# BatmanDetector.net
KiCad netlist of a schematic drawn in EAGLE
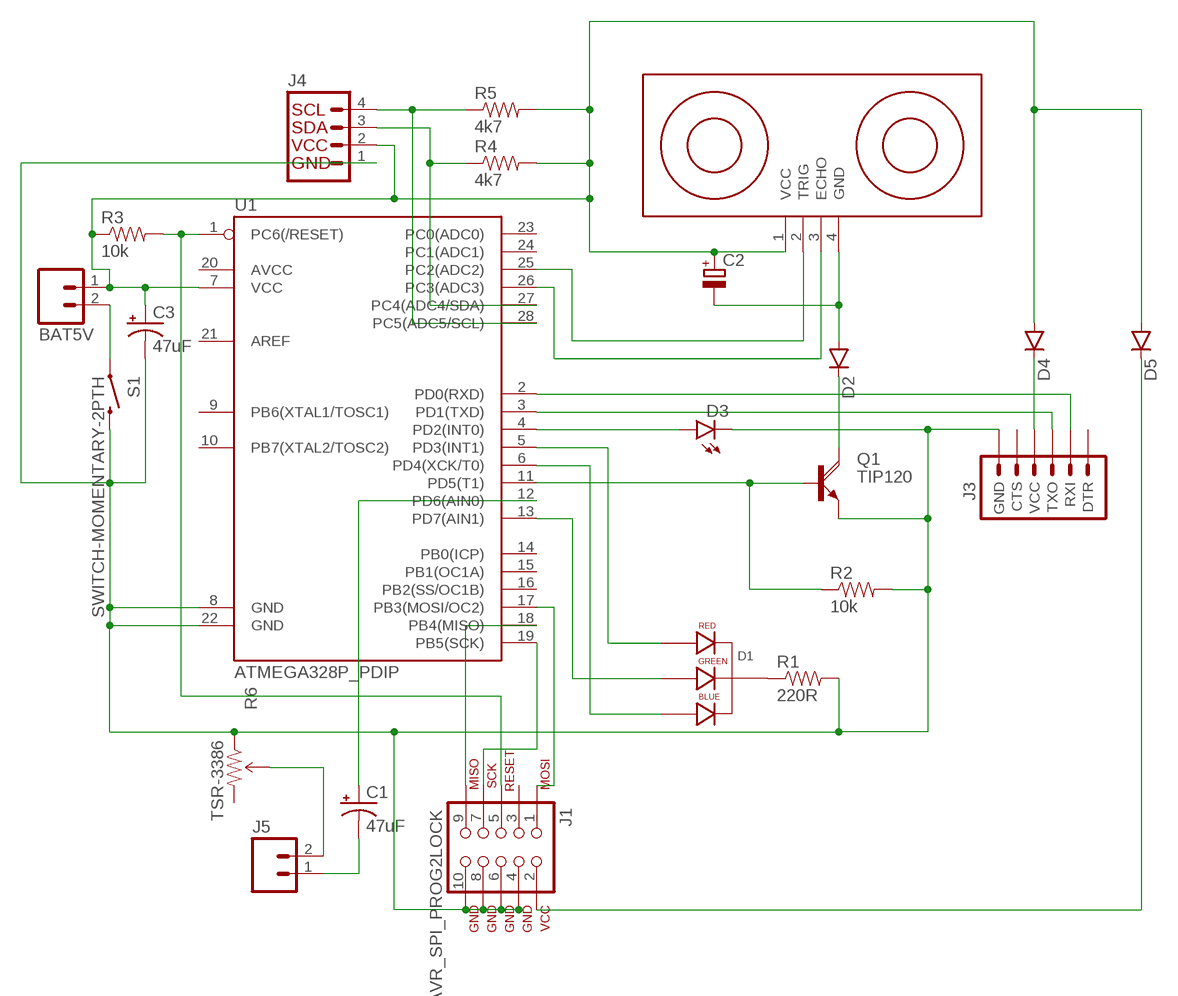
[diagram p0: schematic, sheet 1]

(export (version "E")
  (design (tool "Eeschema 10.0.6"))
  (components
    (comp (ref "BAT5V")
      (value "M02JST-PTH-VERT")
      (footprint "eagle-import:JST-2-PTH-VERT")
      (libsource (lib "eagle-import") (part "M02JST-PTH-VERT"))
    )
    (comp (ref "C1")
      (value "47uF")
      (footprint "eagle-import:CPOL-RADIAL-10UF-25V")
      (libsource (lib "eagle-import") (part "CAP_POLPTH2"))
    )
    (comp (ref "C2")
      (value "CPOL-EUE15-5AXIAL")
      (footprint "eagle-import:E15-5")
      (libsource (lib "eagle-import") (part "CPOL-EUE15-5AXIAL"))
    )
    (comp (ref "C3")
      (value "47uF")
      (footprint "eagle-import:CPOL-RADIAL-10UF-25V")
      (libsource (lib "eagle-import") (part "CAP_POLPTH2"))
    )
    (comp (ref "D1")
      (value "LED-RGB-CC-THRUDIFFUSE")
      (footprint "eagle-import:LED-RGB-THRU")
      (libsource (lib "eagle-import") (part "LED-RGB-CC-THRUDIFFUSE"))
    )
    (comp (ref "D2")
      (value "DIODE1N4148")
      (footprint "eagle-import:DIODE-1N4148")
      (libsource (lib "eagle-import") (part "DIODE1N4148"))
    )
    (comp (ref "D3")
      (value "LED-3MM-NO_SILK")
      (footprint "eagle-import:LED3MM-NS")
      (libsource (lib "eagle-import") (part "LED-3MM-NO_SILK"))
    )
    (comp (ref "D4")
      (value "DIODE1N4148")
      (footprint "eagle-import:DIODE-1N4148")
      (libsource (lib "eagle-import") (part "DIODE1N4148"))
    )
    (comp (ref "D5")
      (value "DIODE1N4148")
      (footprint "eagle-import:DIODE-1N4148")
      (libsource (lib "eagle-import") (part "DIODE1N4148"))
    )
    (comp (ref "J1")
      (value "AVR_SPI_PROG2LOCK")
      (footprint "eagle-import:2X5-SHROUDED_LOCK")
      (libsource (lib "eagle-import") (part "AVR_SPI_PROG2LOCK"))
    )
    (comp (ref "J3")
      (value "ARDUINO_SERIAL_PROGRAMLONGPADS")
      (footprint "eagle-import:1X06_LONGPADS")
      (libsource (lib "eagle-import") (part "ARDUINO_SERIAL_PROGRAMLONGPADS"))
    )
    (comp (ref "J4")
      (value "I2C_STANDARD_NO_SILK")
      (footprint "eagle-import:1X04_NO_SILK")
      (libsource (lib "eagle-import") (part "I2C_STANDARD_NO_SILK"))
    )
    (comp (ref "J5")
      (value "M02PTH3")
      (footprint "eagle-import:1X02_LONGPADS")
      (libsource (lib "eagle-import") (part "M02PTH3"))
    )
    (comp (ref "Q1")
      (value "TIP120")
      (footprint "eagle-import:TO220AH")
      (libsource (lib "eagle-import") (part "TIP120"))
    )
    (comp (ref "R1")
      (value "220R")
      (footprint "eagle-import:AXIAL-0.3")
      (libsource (lib "eagle-import") (part "RESISTORAXIAL-0.3"))
    )
    (comp (ref "R2")
      (value "10k")
      (footprint "eagle-import:AXIAL-0.3")
      (libsource (lib "eagle-import") (part "RESISTORAXIAL-0.3"))
    )
    (comp (ref "R3")
      (value "10k")
      (footprint "eagle-import:AXIAL-0.3")
      (libsource (lib "eagle-import") (part "RESISTORAXIAL-0.3"))
    )
    (comp (ref "R4")
      (value "4k7")
      (footprint "eagle-import:AXIAL-0.3")
      (libsource (lib "eagle-import") (part "RESISTORAXIAL-0.3"))
    )
    (comp (ref "R5")
      (value "4k7")
      (footprint "eagle-import:AXIAL-0.3")
      (libsource (lib "eagle-import") (part "RESISTORAXIAL-0.3"))
    )
    (comp (ref "R6")
      (value "TSR-3386")
      (footprint "eagle-import:3386U")
      (libsource (lib "eagle-import") (part "TRIMPOT-PTH-KNOB"))
    )
    (comp (ref "S1")
      (value "SWITCH-MOMENTARY-2PTH")
      (footprint "eagle-import:TACTILE-PTH")
      (libsource (lib "eagle-import") (part "SWITCH-MOMENTARY-2PTH"))
    )
    (comp (ref "U$1")
      (value "ULTRASONIC-HC-SR04#V")
      (footprint "eagle-import:ULTRASONIC-HC-SR04#V")
      (libsource (lib "eagle-import") (part "ULTRASONIC-HC-SR04#V"))
    )
    (comp (ref "U1")
      (value "ATMEGA328P_PDIP")
      (footprint "eagle-import:DIL28-3")
      (libsource (lib "eagle-import") (part "ATMEGA328P_PDIP"))
    )
  )
  (nets
    (net (code "1") (name "Net-(BAT5V-Pad2)") (class "Default")
      (node (ref "BAT5V") (pin "2") (pinfunction "2_2") (pintype "passive"))
      (node (ref "S1") (pin "1") (pinfunction "1_1") (pintype "passive"))
    )
    (net (code "2") (name "Net-(C1-+)") (class "Default")
      (node (ref "C1") (pin "1") (pinfunction "+_1") (pintype "passive"))
      (node (ref "U1") (pin "12") (pinfunction "PD6(AIN0)_12") (pintype "bidirectional"))
    )
    (net (code "3") (name "Net-(C1--)") (class "Default")
      (node (ref "C1") (pin "2") (pinfunction "-_2") (pintype "passive"))
      (node (ref "J5") (pin "1") (pinfunction "1_1") (pintype "passive"))
    )
    (net (code "4") (name "Net-(C3-+)") (class "Default")
      (node (ref "BAT5V") (pin "1") (pinfunction "1_1") (pintype "passive"))
      (node (ref "C2") (pin "+") (pinfunction "+_+") (pintype "passive"))
      (node (ref "C3") (pin "1") (pinfunction "+_1") (pintype "passive"))
      (node (ref "D4") (pin "A") (pinfunction "A_A") (pintype "passive"))
      (node (ref "D5") (pin "A") (pinfunction "A_A") (pintype "passive"))
      (node (ref "J4") (pin "2") (pinfunction "2_2") (pintype "passive"))
      (node (ref "R3") (pin "P$1") (pinfunction "1_P$1") (pintype "passive"))
      (node (ref "R4") (pin "P$2") (pinfunction "2_P$2") (pintype "passive"))
      (node (ref "R5") (pin "P$2") (pinfunction "2_P$2") (pintype "passive"))
      (node (ref "U$1") (pin "1") (pinfunction "VCC_1") (pintype "power_in"))
      (node (ref "U1") (pin "7") (pinfunction "VCC_7") (pintype "bidirectional"))
    )
    (net (code "5") (name "Net-(C3--)") (class "Default")
      (node (ref "C3") (pin "2") (pinfunction "-_2") (pintype "passive"))
      (node (ref "D3") (pin "K") (pinfunction "C_K") (pintype "passive"))
      (node (ref "J1") (pin "10") (pinfunction "GND_10") (pintype "power_in"))
      (node (ref "J1") (pin "4") (pinfunction "GND_4") (pintype "power_in"))
      (node (ref "J1") (pin "6") (pinfunction "GND_6") (pintype "power_in"))
      (node (ref "J1") (pin "8") (pinfunction "GND_8") (pintype "power_in"))
      (node (ref "J3") (pin "6") (pinfunction "GND_6") (pintype "passive"))
      (node (ref "J4") (pin "1") (pinfunction "1_1") (pintype "passive"))
      (node (ref "Q1") (pin "E") (pinfunction "E_E") (pintype "passive"))
      (node (ref "R1") (pin "P$2") (pinfunction "2_P$2") (pintype "passive"))
      (node (ref "R2") (pin "P$2") (pinfunction "2_P$2") (pintype "passive"))
      (node (ref "R6") (pin "1") (pinfunction "CCW_1") (pintype "passive"))
      (node (ref "S1") (pin "3") (pinfunction "2_3") (pintype "passive"))
      (node (ref "U1") (pin "22") (pinfunction "GND_22") (pintype "bidirectional"))
      (node (ref "U1") (pin "8") (pinfunction "GND_8") (pintype "bidirectional"))
    )
    (net (code "6") (name "Net-(D1-BLUE_CATHODE)") (class "Default")
      (node (ref "D1") (pin "4") (pinfunction "BLUE_CATHODE_4") (pintype "bidirectional"))
      (node (ref "U1") (pin "6") (pinfunction "PD4(XCK/T0)_6") (pintype "bidirectional"))
    )
    (net (code "7") (name "Net-(D1-CATHODE)") (class "Default")
      (node (ref "D1") (pin "2") (pinfunction "CATHODE_2") (pintype "bidirectional"))
      (node (ref "R1") (pin "P$1") (pinfunction "1_P$1") (pintype "passive"))
    )
    (net (code "8") (name "Net-(D1-GREEN_CATHODE)") (class "Default")
      (node (ref "D1") (pin "3") (pinfunction "GREEN_CATHODE_3") (pintype "bidirectional"))
      (node (ref "U1") (pin "13") (pinfunction "PD7(AIN1)_13") (pintype "bidirectional"))
    )
    (net (code "9") (name "Net-(D1-RED_CATHODE)") (class "Default")
      (node (ref "D1") (pin "1") (pinfunction "RED_CATHODE_1") (pintype "bidirectional"))
      (node (ref "U1") (pin "5") (pinfunction "PD3(INT1)_5") (pintype "bidirectional"))
    )
    (net (code "10") (name "Net-(D2-PadC)") (class "Default")
      (node (ref "D2") (pin "C") (pinfunction "C_C") (pintype "passive"))
      (node (ref "Q1") (pin "C") (pinfunction "C_C") (pintype "passive"))
    )
    (net (code "11") (name "Net-(J1-MISO)") (class "Default")
      (node (ref "J1") (pin "9") (pinfunction "MISO_9") (pintype "passive"))
      (node (ref "U1") (pin "18") (pinfunction "PB4(MISO)_18") (pintype "bidirectional"))
    )
    (net (code "12") (name "Net-(J1-MOSI)") (class "Default")
      (node (ref "J1") (pin "1") (pinfunction "MOSI_1") (pintype "passive"))
      (node (ref "U1") (pin "17") (pinfunction "PB3(MOSI/OC2)_17") (pintype "bidirectional"))
    )
    (net (code "13") (name "Net-(J1-RESET)") (class "Default")
      (node (ref "J1") (pin "5") (pinfunction "RESET_5") (pintype "passive"))
      (node (ref "R3") (pin "P$2") (pinfunction "2_P$2") (pintype "passive"))
      (node (ref "U1") (pin "1") (pinfunction "PC6(/RESET)_1") (pintype "bidirectional"))
    )
    (net (code "14") (name "Net-(J1-SCK)") (class "Default")
      (node (ref "J1") (pin "7") (pinfunction "SCK_7") (pintype "passive"))
      (node (ref "U1") (pin "19") (pinfunction "PB5(SCK)_19") (pintype "bidirectional"))
    )
    (net (code "15") (name "Net-(J1-VCC)") (class "Default")
      (node (ref "D5") (pin "C") (pinfunction "C_C") (pintype "passive"))
      (node (ref "J1") (pin "2") (pinfunction "VCC_2") (pintype "power_in"))
    )
    (net (code "16") (name "Net-(J3-RXI)") (class "Default")
      (node (ref "J3") (pin "2") (pinfunction "RXI_2") (pintype "passive"))
      (node (ref "U1") (pin "2") (pinfunction "PD0(RXD)_2") (pintype "bidirectional"))
    )
    (net (code "17") (name "Net-(J3-TXO)") (class "Default")
      (node (ref "J3") (pin "3") (pinfunction "TXO_3") (pintype "passive"))
      (node (ref "U1") (pin "3") (pinfunction "PD1(TXD)_3") (pintype "bidirectional"))
    )
    (net (code "18") (name "Net-(J3-VCC)") (class "Default")
      (node (ref "D4") (pin "C") (pinfunction "C_C") (pintype "passive"))
      (node (ref "J3") (pin "4") (pinfunction "VCC_4") (pintype "passive"))
    )
    (net (code "19") (name "Net-(R2-1)") (class "Default")
      (node (ref "Q1") (pin "B") (pinfunction "B_B") (pintype "passive"))
      (node (ref "R2") (pin "P$1") (pinfunction "1_P$1") (pintype "passive"))
      (node (ref "U1") (pin "11") (pinfunction "PD5(T1)_11") (pintype "bidirectional"))
    )
    (net (code "20") (name "Net-(R4-1)") (class "Default")
      (node (ref "J4") (pin "3") (pinfunction "3_3") (pintype "passive"))
      (node (ref "R4") (pin "P$1") (pinfunction "1_P$1") (pintype "passive"))
      (node (ref "U1") (pin "27") (pinfunction "PC4(ADC4/SDA)_27") (pintype "bidirectional"))
    )
    (net (code "21") (name "Net-(R5-1)") (class "Default")
      (node (ref "J4") (pin "4") (pinfunction "4_4") (pintype "passive"))
      (node (ref "R5") (pin "P$1") (pinfunction "1_P$1") (pintype "passive"))
      (node (ref "U1") (pin "28") (pinfunction "PC5(ADC5/SCL)_28") (pintype "bidirectional"))
    )
    (net (code "22") (name "Net-(R6-WIPER)") (class "Default")
      (node (ref "J5") (pin "2") (pinfunction "2_2") (pintype "passive"))
      (node (ref "R6") (pin "2") (pinfunction "WIPER_2") (pintype "passive"))
    )
    (net (code "23") (name "Net-(U$1-ECHO)") (class "Default")
      (node (ref "U$1") (pin "3") (pinfunction "ECHO_3") (pintype "output"))
      (node (ref "U1") (pin "26") (pinfunction "PC3(ADC3)_26") (pintype "bidirectional"))
    )
    (net (code "24") (name "Net-(U$1-GND)") (class "Default")
      (node (ref "C2") (pin "-") (pinfunction "-_-") (pintype "passive"))
      (node (ref "D2") (pin "A") (pinfunction "A_A") (pintype "passive"))
      (node (ref "U$1") (pin "4") (pinfunction "GND_4") (pintype "power_in"))
    )
    (net (code "25") (name "Net-(U$1-TRIG)") (class "Default")
      (node (ref "U$1") (pin "2") (pinfunction "TRIG_2") (pintype "input"))
      (node (ref "U1") (pin "25") (pinfunction "PC2(ADC2)_25") (pintype "bidirectional"))
    )
    (net (code "26") (name "Net-(U1-PD2(INT0))") (class "Default")
      (node (ref "D3") (pin "A") (pinfunction "A_A") (pintype "passive"))
      (node (ref "U1") (pin "4") (pinfunction "PD2(INT0)_4") (pintype "bidirectional"))
    )
    (net (code "27") (name "unconnected-(J1-NC-Pad3)") (class "Default")
      (node (ref "J1") (pin "3") (pinfunction "NC_3") (pintype "no_connect"))
    )
    (net (code "28") (name "unconnected-(J3-CTS-Pad5)") (class "Default")
      (node (ref "J3") (pin "5") (pinfunction "CTS_5") (pintype "passive"))
    )
    (net (code "29") (name "unconnected-(J3-DTR-Pad1)") (class "Default")
      (node (ref "J3") (pin "1") (pinfunction "DTR_1") (pintype "passive"))
    )
    (net (code "30") (name "unconnected-(R6-CW-Pad3)") (class "Default")
      (node (ref "R6") (pin "3") (pinfunction "CW_3") (pintype "passive"))
    )
    (net (code "31") (name "unconnected-(U1-AREF-Pad21)") (class "Default")
      (node (ref "U1") (pin "21") (pinfunction "AREF_21") (pintype "bidirectional"))
    )
    (net (code "32") (name "unconnected-(U1-AVCC-Pad20)") (class "Default")
      (node (ref "U1") (pin "20") (pinfunction "AVCC_20") (pintype "bidirectional"))
    )
    (net (code "33") (name "unconnected-(U1-PB0(ICP)-Pad14)") (class "Default")
      (node (ref "U1") (pin "14") (pinfunction "PB0(ICP)_14") (pintype "bidirectional"))
    )
    (net (code "34") (name "unconnected-(U1-PB1(OC1A)-Pad15)") (class "Default")
      (node (ref "U1") (pin "15") (pinfunction "PB1(OC1A)_15") (pintype "bidirectional"))
    )
    (net (code "35") (name "unconnected-(U1-PB2(SS{slash}OC1B)-Pad16)") (class "Default")
      (node (ref "U1") (pin "16") (pinfunction "PB2(SS/OC1B)_16") (pintype "bidirectional"))
    )
    (net (code "36") (name "unconnected-(U1-PB6(XTAL1{slash}TOSC1)-Pad9)") (class "Default")
      (node (ref "U1") (pin "9") (pinfunction "PB6(XTAL1/TOSC1)_9") (pintype "bidirectional"))
    )
    (net (code "37") (name "unconnected-(U1-PB7(XTAL2{slash}TOSC2)-Pad10)") (class "Default")
      (node (ref "U1") (pin "10") (pinfunction "PB7(XTAL2/TOSC2)_10") (pintype "bidirectional"))
    )
    (net (code "38") (name "unconnected-(U1-PC0(ADC0)-Pad23)") (class "Default")
      (node (ref "U1") (pin "23") (pinfunction "PC0(ADC0)_23") (pintype "bidirectional"))
    )
    (net (code "39") (name "unconnected-(U1-PC1(ADC1)-Pad24)") (class "Default")
      (node (ref "U1") (pin "24") (pinfunction "PC1(ADC1)_24") (pintype "bidirectional"))
    )
  )
)
